# TEST_BED_BATT_BUTTONS.net
KiCad netlist of a schematic drawn in EAGLE
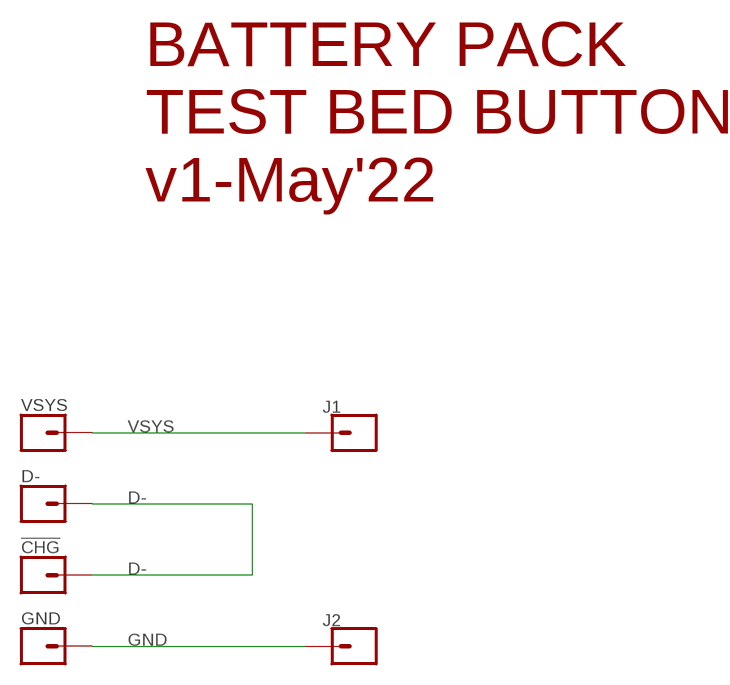
[diagram p0: schematic, sheet 1]

(export (version "E")
  (design (tool "Eeschema 10.0.6"))
  (components
    (comp (ref "!CHG")
      (value "CONN_01POGOPIN_HOLE_LARGE")
      (footprint "eagle-import:1X01_POGOPIN_HOLE_0.061_DIA")
      (libsource (lib "eagle-import") (part "CONN_01POGOPIN_HOLE_LARGE"))
    )
    (comp (ref "D-")
      (value "CONN_01POGOPIN_HOLE_LARGE")
      (footprint "eagle-import:1X01_POGOPIN_HOLE_0.061_DIA")
      (libsource (lib "eagle-import") (part "CONN_01POGOPIN_HOLE_LARGE"))
    )
    (comp (ref "GND")
      (value "CONN_01POGOPIN_HOLE_LARGE")
      (footprint "eagle-import:1X01_POGOPIN_HOLE_0.061_DIA")
      (libsource (lib "eagle-import") (part "CONN_01POGOPIN_HOLE_LARGE"))
    )
    (comp (ref "J1")
      (value "CONN_01PTH_2MM")
      (footprint "eagle-import:1X01_2MM")
      (libsource (lib "eagle-import") (part "SparkFun-Connectors_513_CONN_01PTH_2MM"))
    )
    (comp (ref "J2")
      (value "CONN_01PTH_2MM")
      (footprint "eagle-import:1X01_2MM")
      (libsource (lib "eagle-import") (part "SparkFun-Connectors_513_CONN_01PTH_2MM"))
    )
    (comp (ref "VSYS")
      (value "CONN_01POGOPIN_HOLE_LARGE")
      (footprint "eagle-import:1X01_POGOPIN_HOLE_0.061_DIA")
      (libsource (lib "eagle-import") (part "CONN_01POGOPIN_HOLE_LARGE"))
    )
  )
  (nets
    (net (code "1") (name "/D-") (class "Default")
      (node (ref "!CHG") (pin "2") (pinfunction "1_2") (pintype "passive"))
      (node (ref "D-") (pin "2") (pinfunction "1_2") (pintype "passive"))
    )
    (net (code "2") (name "/GND") (class "Default")
      (node (ref "GND") (pin "2") (pinfunction "1_2") (pintype "passive"))
      (node (ref "J2") (pin "1") (pinfunction "1_1") (pintype "passive"))
    )
    (net (code "3") (name "/VSYS") (class "Default")
      (node (ref "J1") (pin "1") (pinfunction "1_1") (pintype "passive"))
      (node (ref "VSYS") (pin "2") (pinfunction "1_2") (pintype "passive"))
    )
  )
)
